# design.net
KiCad netlist of a schematic drawn in Altium Designer
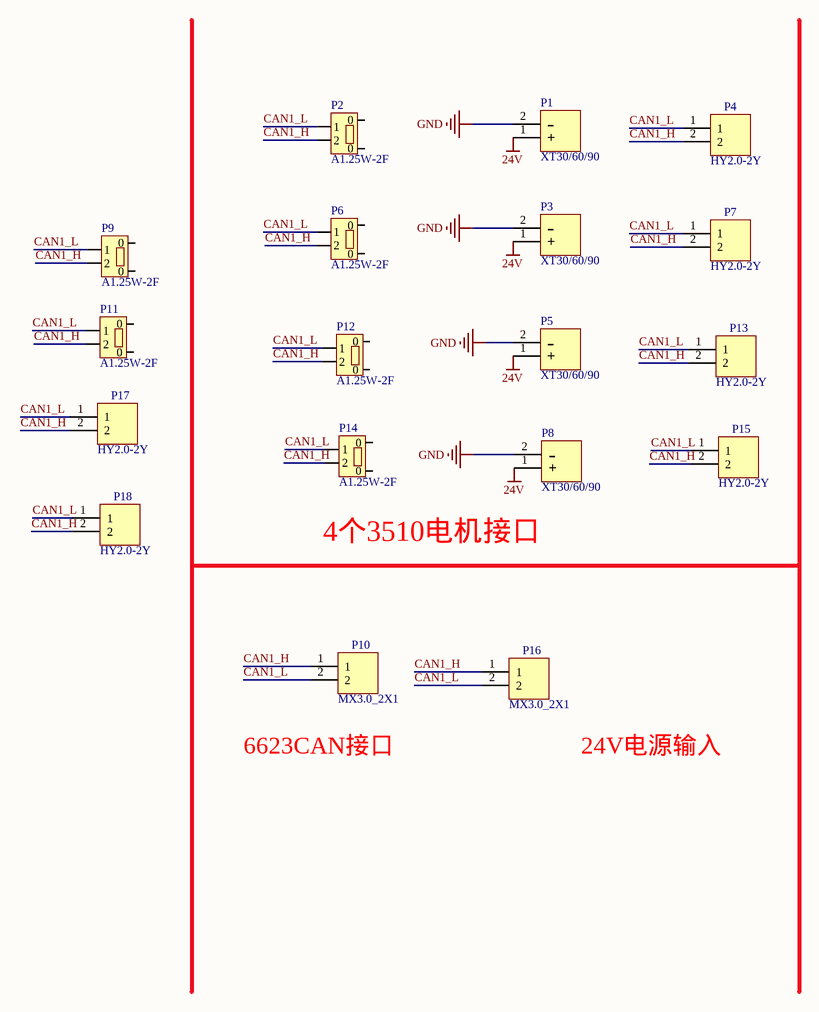
[diagram p0: 中心连接板.SchDoc]

(export (version "E")
  (design (tool "Eeschema 10.0.6"))
  (components
    (comp (ref "P1")
      (value "XT30/60/90")
      (footprint "XT30立式")
      (libsource (lib "MyComponents_v2.4") (part "XT30/60/90"))
    )
    (comp (ref "P2")
      (value "A1.25W-2F")
      (footprint "GH1.25_立式")
      (libsource (lib "MyComponents_v2.5") (part "GH1.25-2P"))
    )
    (comp (ref "P3")
      (value "XT30/60/90")
      (footprint "XT30立式")
      (libsource (lib "MyComponents_v2.4") (part "XT30/60/90"))
    )
    (comp (ref "P4")
      (value "HY2.0-2Y")
      (footprint "HY2.00MM 2X1_立式")
      (libsource (lib "MyComponents") (part "MX3.0_2X1"))
    )
    (comp (ref "P5")
      (value "XT30/60/90")
      (footprint "XT30立式")
      (libsource (lib "MyComponents_v2.4") (part "XT30/60/90"))
    )
    (comp (ref "P6")
      (value "A1.25W-2F")
      (footprint "GH1.25_立式")
      (libsource (lib "MyComponents_v2.5") (part "GH1.25-2P"))
    )
    (comp (ref "P7")
      (value "HY2.0-2Y")
      (footprint "HY2.00MM 2X1_立式")
      (libsource (lib "MyComponents") (part "MX3.0_2X1"))
    )
    (comp (ref "P8")
      (value "XT30/60/90")
      (footprint "XT30立式")
      (libsource (lib "MyComponents_v2.4") (part "XT30/60/90"))
    )
    (comp (ref "P9")
      (value "A1.25W-2F")
      (footprint "GH1.25_立式")
      (libsource (lib "MyComponents_v2.5") (part "GH1.25-2P"))
    )
    (comp (ref "P10")
      (value "MX3.0_2X1")
      (footprint "MX3.0_2X1_立式")
      (libsource (lib "MyComponents") (part "MX3.0_2X1"))
    )
    (comp (ref "P11")
      (value "A1.25W-2F")
      (footprint "GH1.25_立式")
      (libsource (lib "MyComponents_v2.5") (part "GH1.25-2P"))
    )
    (comp (ref "P12")
      (value "A1.25W-2F")
      (footprint "GH1.25_立式")
      (libsource (lib "MyComponents_v2.5") (part "GH1.25-2P"))
    )
    (comp (ref "P13")
      (value "HY2.0-2Y")
      (footprint "HY2.00MM 2X1_立式")
      (libsource (lib "MyComponents") (part "MX3.0_2X1"))
    )
    (comp (ref "P14")
      (value "A1.25W-2F")
      (footprint "GH1.25_立式")
      (libsource (lib "MyComponents_v2.5") (part "GH1.25-2P"))
    )
    (comp (ref "P15")
      (value "HY2.0-2Y")
      (footprint "HY2.00MM 2X1_立式")
      (libsource (lib "MyComponents") (part "MX3.0_2X1"))
    )
    (comp (ref "P16")
      (value "MX3.0_2X1")
      (footprint "MX3.0_2X1_立式")
      (libsource (lib "MyComponents") (part "MX3.0_2X1"))
    )
    (comp (ref "P17")
      (value "HY2.0-2Y")
      (footprint "HY2.00MM 2X1_立式")
      (libsource (lib "MyComponents") (part "MX3.0_2X1"))
    )
    (comp (ref "P18")
      (value "HY2.0-2Y")
      (footprint "HY2.00MM 2X1_立式")
      (libsource (lib "MyComponents") (part "MX3.0_2X1"))
    )
  )
  (nets
    (net (code "1") (name "/CAN1_H") (class "Default")
      (node (ref "P10") (pin "1") (pinfunction "1_1") (pintype "passive"))
      (node (ref "P11") (pin "2") (pinfunction "2_2") (pintype "passive"))
      (node (ref "P12") (pin "2") (pinfunction "2_2") (pintype "passive"))
      (node (ref "P13") (pin "2") (pinfunction "2_2") (pintype "passive"))
      (node (ref "P14") (pin "2") (pinfunction "2_2") (pintype "passive"))
      (node (ref "P15") (pin "2") (pinfunction "2_2") (pintype "passive"))
      (node (ref "P16") (pin "1") (pinfunction "1_1") (pintype "passive"))
      (node (ref "P17") (pin "2") (pinfunction "2_2") (pintype "passive"))
      (node (ref "P18") (pin "2") (pinfunction "2_2") (pintype "passive"))
      (node (ref "P2") (pin "2") (pinfunction "2_2") (pintype "passive"))
      (node (ref "P4") (pin "2") (pinfunction "2_2") (pintype "passive"))
      (node (ref "P6") (pin "2") (pinfunction "2_2") (pintype "passive"))
      (node (ref "P7") (pin "2") (pinfunction "2_2") (pintype "passive"))
      (node (ref "P9") (pin "2") (pinfunction "2_2") (pintype "passive"))
    )
    (net (code "2") (name "/CAN1_L") (class "Default")
      (node (ref "P10") (pin "2") (pinfunction "2_2") (pintype "passive"))
      (node (ref "P11") (pin "1") (pinfunction "1_1") (pintype "passive"))
      (node (ref "P12") (pin "1") (pinfunction "1_1") (pintype "passive"))
      (node (ref "P13") (pin "1") (pinfunction "1_1") (pintype "passive"))
      (node (ref "P14") (pin "1") (pinfunction "1_1") (pintype "passive"))
      (node (ref "P15") (pin "1") (pinfunction "1_1") (pintype "passive"))
      (node (ref "P16") (pin "2") (pinfunction "2_2") (pintype "passive"))
      (node (ref "P17") (pin "1") (pinfunction "1_1") (pintype "passive"))
      (node (ref "P18") (pin "1") (pinfunction "1_1") (pintype "passive"))
      (node (ref "P2") (pin "1") (pinfunction "1_1") (pintype "passive"))
      (node (ref "P4") (pin "1") (pinfunction "1_1") (pintype "passive"))
      (node (ref "P6") (pin "1") (pinfunction "1_1") (pintype "passive"))
      (node (ref "P7") (pin "1") (pinfunction "1_1") (pintype "passive"))
      (node (ref "P9") (pin "1") (pinfunction "1_1") (pintype "passive"))
    )
    (net (code "3") (name "24V") (class "Default")
      (node (ref "P1") (pin "1") (pinfunction "+_1") (pintype "passive"))
      (node (ref "P3") (pin "1") (pinfunction "+_1") (pintype "passive"))
      (node (ref "P5") (pin "1") (pinfunction "+_1") (pintype "passive"))
      (node (ref "P8") (pin "1") (pinfunction "+_1") (pintype "passive"))
    )
    (net (code "4") (name "GND") (class "Default")
      (node (ref "P1") (pin "2") (pinfunction "-_2") (pintype "passive"))
      (node (ref "P3") (pin "2") (pinfunction "-_2") (pintype "passive"))
      (node (ref "P5") (pin "2") (pinfunction "-_2") (pintype "passive"))
      (node (ref "P8") (pin "2") (pinfunction "-_2") (pintype "passive"))
    )
    (net (code "5") (name "unconnected-(P2-Pad0)") (class "Default")
      (node (ref "P2") (pin "0") (pinfunction "0_0") (pintype "passive"))
    )
    (net (code "6") (name "unconnected-(P2-Pad0)_1") (class "Default")
      (node (ref "P2") (pin "0") (pinfunction "0_0") (pintype "passive"))
    )
    (net (code "7") (name "unconnected-(P6-Pad0)") (class "Default")
      (node (ref "P6") (pin "0") (pinfunction "0_0") (pintype "passive"))
    )
    (net (code "8") (name "unconnected-(P6-Pad0)_1") (class "Default")
      (node (ref "P6") (pin "0") (pinfunction "0_0") (pintype "passive"))
    )
    (net (code "9") (name "unconnected-(P9-Pad0)") (class "Default")
      (node (ref "P9") (pin "0") (pinfunction "0_0") (pintype "passive"))
    )
    (net (code "10") (name "unconnected-(P9-Pad0)_1") (class "Default")
      (node (ref "P9") (pin "0") (pinfunction "0_0") (pintype "passive"))
    )
    (net (code "11") (name "unconnected-(P11-Pad0)") (class "Default")
      (node (ref "P11") (pin "0") (pinfunction "0_0") (pintype "passive"))
    )
    (net (code "12") (name "unconnected-(P11-Pad0)_1") (class "Default")
      (node (ref "P11") (pin "0") (pinfunction "0_0") (pintype "passive"))
    )
    (net (code "13") (name "unconnected-(P12-Pad0)") (class "Default")
      (node (ref "P12") (pin "0") (pinfunction "0_0") (pintype "passive"))
    )
    (net (code "14") (name "unconnected-(P12-Pad0)_1") (class "Default")
      (node (ref "P12") (pin "0") (pinfunction "0_0") (pintype "passive"))
    )
    (net (code "15") (name "unconnected-(P14-Pad0)") (class "Default")
      (node (ref "P14") (pin "0") (pinfunction "0_0") (pintype "passive"))
    )
    (net (code "16") (name "unconnected-(P14-Pad0)_1") (class "Default")
      (node (ref "P14") (pin "0") (pinfunction "0_0") (pintype "passive"))
    )
  )
)
